# Heater_subassembly_revA.net
KiCad netlist of a schematic drawn in EAGLE
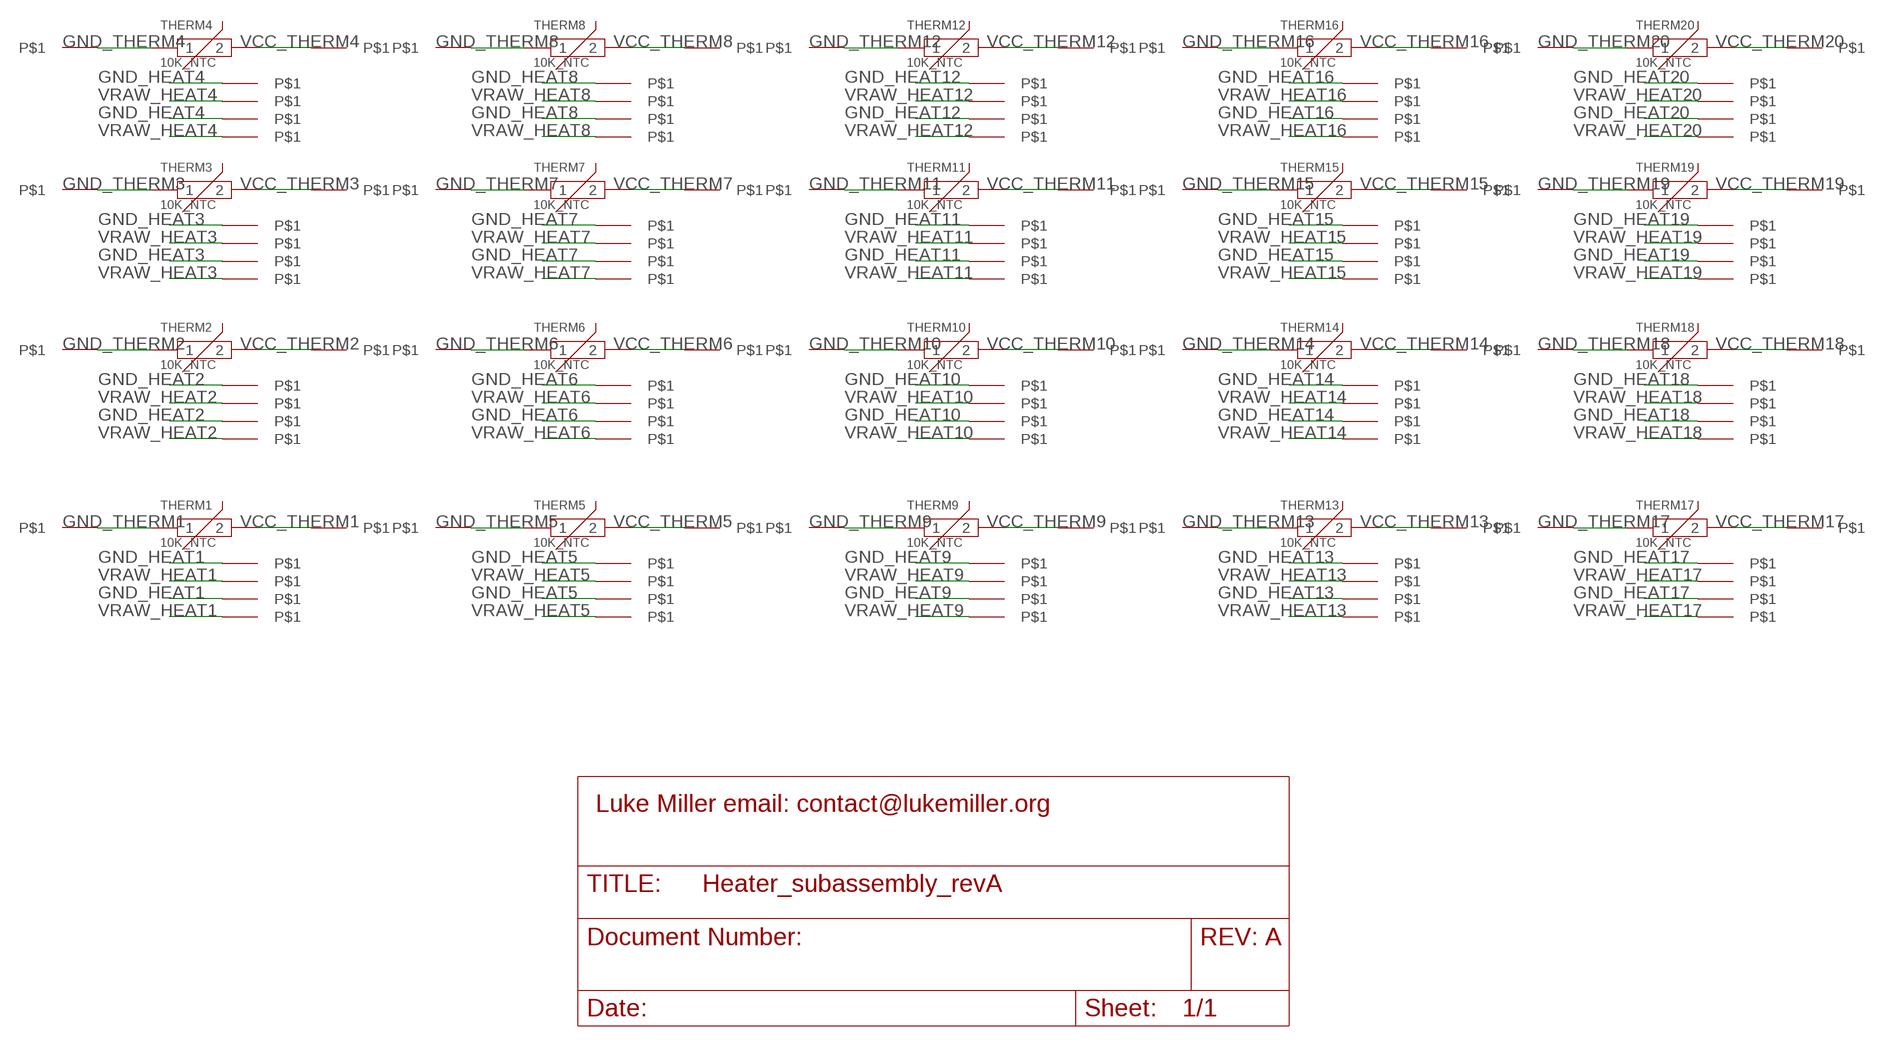
[diagram p0: schematic, sheet 1]

(export (version "E")
  (design (tool "Eeschema 10.0.6"))
  (components
    (comp (ref "GND_HEAT1")
      (value "PINHD-1X1SMALL")
      (footprint "eagle-import:1X01_SMALL")
      (libsource (lib "eagle-import") (part "PINHD-1X1SMALL"))
    )
    (comp (ref "GND_HEAT2")
      (value "PINHD-1X1SMALL")
      (footprint "eagle-import:1X01_SMALL")
      (libsource (lib "eagle-import") (part "PINHD-1X1SMALL"))
    )
    (comp (ref "GND_HEAT3")
      (value "PINHD-1X1SMALL")
      (footprint "eagle-import:1X01_SMALL")
      (libsource (lib "eagle-import") (part "PINHD-1X1SMALL"))
    )
    (comp (ref "GND_HEAT4")
      (value "PINHD-1X1SMALL")
      (footprint "eagle-import:1X01_SMALL")
      (libsource (lib "eagle-import") (part "PINHD-1X1SMALL"))
    )
    (comp (ref "GND_HEAT5")
      (value "PINHD-1X1SMALL")
      (footprint "eagle-import:1X01_SMALL")
      (libsource (lib "eagle-import") (part "PINHD-1X1SMALL"))
    )
    (comp (ref "GND_HEAT6")
      (value "PINHD-1X1SMALL")
      (footprint "eagle-import:1X01_SMALL")
      (libsource (lib "eagle-import") (part "PINHD-1X1SMALL"))
    )
    (comp (ref "GND_HEAT7")
      (value "PINHD-1X1SMALL")
      (footprint "eagle-import:1X01_SMALL")
      (libsource (lib "eagle-import") (part "PINHD-1X1SMALL"))
    )
    (comp (ref "GND_HEAT8")
      (value "PINHD-1X1SMALL")
      (footprint "eagle-import:1X01_SMALL")
      (libsource (lib "eagle-import") (part "PINHD-1X1SMALL"))
    )
    (comp (ref "GND_HEAT9")
      (value "PINHD-1X1SMALL")
      (footprint "eagle-import:1X01_SMALL")
      (libsource (lib "eagle-import") (part "PINHD-1X1SMALL"))
    )
    (comp (ref "GND_HEAT10")
      (value "PINHD-1X1SMALL")
      (footprint "eagle-import:1X01_SMALL")
      (libsource (lib "eagle-import") (part "PINHD-1X1SMALL"))
    )
    (comp (ref "GND_HEAT11")
      (value "PINHD-1X1SMALL")
      (footprint "eagle-import:1X01_SMALL")
      (libsource (lib "eagle-import") (part "PINHD-1X1SMALL"))
    )
    (comp (ref "GND_HEAT12")
      (value "PINHD-1X1SMALL")
      (footprint "eagle-import:1X01_SMALL")
      (libsource (lib "eagle-import") (part "PINHD-1X1SMALL"))
    )
    (comp (ref "GND_HEAT13")
      (value "PINHD-1X1SMALL")
      (footprint "eagle-import:1X01_SMALL")
      (libsource (lib "eagle-import") (part "PINHD-1X1SMALL"))
    )
    (comp (ref "GND_HEAT14")
      (value "PINHD-1X1SMALL")
      (footprint "eagle-import:1X01_SMALL")
      (libsource (lib "eagle-import") (part "PINHD-1X1SMALL"))
    )
    (comp (ref "GND_HEAT15")
      (value "PINHD-1X1SMALL")
      (footprint "eagle-import:1X01_SMALL")
      (libsource (lib "eagle-import") (part "PINHD-1X1SMALL"))
    )
    (comp (ref "GND_HEAT16")
      (value "PINHD-1X1SMALL")
      (footprint "eagle-import:1X01_SMALL")
      (libsource (lib "eagle-import") (part "PINHD-1X1SMALL"))
    )
    (comp (ref "GND_HEAT17")
      (value "PINHD-1X1SMALL")
      (footprint "eagle-import:1X01_SMALL")
      (libsource (lib "eagle-import") (part "PINHD-1X1SMALL"))
    )
    (comp (ref "GND_HEAT18")
      (value "PINHD-1X1SMALL")
      (footprint "eagle-import:1X01_SMALL")
      (libsource (lib "eagle-import") (part "PINHD-1X1SMALL"))
    )
    (comp (ref "GND_HEAT19")
      (value "PINHD-1X1SMALL")
      (footprint "eagle-import:1X01_SMALL")
      (libsource (lib "eagle-import") (part "PINHD-1X1SMALL"))
    )
    (comp (ref "GND_HEAT20")
      (value "PINHD-1X1SMALL")
      (footprint "eagle-import:1X01_SMALL")
      (libsource (lib "eagle-import") (part "PINHD-1X1SMALL"))
    )
    (comp (ref "GND_NICHROME1")
      (value "PINHD-1X10.7MM_DRILL")
      (footprint "eagle-import:1X01_SMALL_0.7")
      (libsource (lib "eagle-import") (part "PINHD-1X10.7MM_DRILL"))
    )
    (comp (ref "GND_NICHROME2")
      (value "PINHD-1X10.7MM_DRILL")
      (footprint "eagle-import:1X01_SMALL_0.7")
      (libsource (lib "eagle-import") (part "PINHD-1X10.7MM_DRILL"))
    )
    (comp (ref "GND_NICHROME3")
      (value "PINHD-1X10.7MM_DRILL")
      (footprint "eagle-import:1X01_SMALL_0.7")
      (libsource (lib "eagle-import") (part "PINHD-1X10.7MM_DRILL"))
    )
    (comp (ref "GND_NICHROME4")
      (value "PINHD-1X10.7MM_DRILL")
      (footprint "eagle-import:1X01_SMALL_0.7")
      (libsource (lib "eagle-import") (part "PINHD-1X10.7MM_DRILL"))
    )
    (comp (ref "GND_NICHROME5")
      (value "PINHD-1X10.7MM_DRILL")
      (footprint "eagle-import:1X01_SMALL_0.7")
      (libsource (lib "eagle-import") (part "PINHD-1X10.7MM_DRILL"))
    )
    (comp (ref "GND_NICHROME6")
      (value "PINHD-1X10.7MM_DRILL")
      (footprint "eagle-import:1X01_SMALL_0.7")
      (libsource (lib "eagle-import") (part "PINHD-1X10.7MM_DRILL"))
    )
    (comp (ref "GND_NICHROME7")
      (value "PINHD-1X10.7MM_DRILL")
      (footprint "eagle-import:1X01_SMALL_0.7")
      (libsource (lib "eagle-import") (part "PINHD-1X10.7MM_DRILL"))
    )
    (comp (ref "GND_NICHROME8")
      (value "PINHD-1X10.7MM_DRILL")
      (footprint "eagle-import:1X01_SMALL_0.7")
      (libsource (lib "eagle-import") (part "PINHD-1X10.7MM_DRILL"))
    )
    (comp (ref "GND_NICHROME9")
      (value "PINHD-1X10.7MM_DRILL")
      (footprint "eagle-import:1X01_SMALL_0.7")
      (libsource (lib "eagle-import") (part "PINHD-1X10.7MM_DRILL"))
    )
    (comp (ref "GND_NICHROME10")
      (value "PINHD-1X10.7MM_DRILL")
      (footprint "eagle-import:1X01_SMALL_0.7")
      (libsource (lib "eagle-import") (part "PINHD-1X10.7MM_DRILL"))
    )
    (comp (ref "GND_NICHROME11")
      (value "PINHD-1X10.7MM_DRILL")
      (footprint "eagle-import:1X01_SMALL_0.7")
      (libsource (lib "eagle-import") (part "PINHD-1X10.7MM_DRILL"))
    )
    (comp (ref "GND_NICHROME12")
      (value "PINHD-1X10.7MM_DRILL")
      (footprint "eagle-import:1X01_SMALL_0.7")
      (libsource (lib "eagle-import") (part "PINHD-1X10.7MM_DRILL"))
    )
    (comp (ref "GND_NICHROME13")
      (value "PINHD-1X10.7MM_DRILL")
      (footprint "eagle-import:1X01_SMALL_0.7")
      (libsource (lib "eagle-import") (part "PINHD-1X10.7MM_DRILL"))
    )
    (comp (ref "GND_NICHROME14")
      (value "PINHD-1X10.7MM_DRILL")
      (footprint "eagle-import:1X01_SMALL_0.7")
      (libsource (lib "eagle-import") (part "PINHD-1X10.7MM_DRILL"))
    )
    (comp (ref "GND_NICHROME15")
      (value "PINHD-1X10.7MM_DRILL")
      (footprint "eagle-import:1X01_SMALL_0.7")
      (libsource (lib "eagle-import") (part "PINHD-1X10.7MM_DRILL"))
    )
    (comp (ref "GND_NICHROME16")
      (value "PINHD-1X10.7MM_DRILL")
      (footprint "eagle-import:1X01_SMALL_0.7")
      (libsource (lib "eagle-import") (part "PINHD-1X10.7MM_DRILL"))
    )
    (comp (ref "GND_NICHROME17")
      (value "PINHD-1X10.7MM_DRILL")
      (footprint "eagle-import:1X01_SMALL_0.7")
      (libsource (lib "eagle-import") (part "PINHD-1X10.7MM_DRILL"))
    )
    (comp (ref "GND_NICHROME18")
      (value "PINHD-1X10.7MM_DRILL")
      (footprint "eagle-import:1X01_SMALL_0.7")
      (libsource (lib "eagle-import") (part "PINHD-1X10.7MM_DRILL"))
    )
    (comp (ref "GND_NICHROME19")
      (value "PINHD-1X10.7MM_DRILL")
      (footprint "eagle-import:1X01_SMALL_0.7")
      (libsource (lib "eagle-import") (part "PINHD-1X10.7MM_DRILL"))
    )
    (comp (ref "GND_NICHROME20")
      (value "PINHD-1X10.7MM_DRILL")
      (footprint "eagle-import:1X01_SMALL_0.7")
      (libsource (lib "eagle-import") (part "PINHD-1X10.7MM_DRILL"))
    )
    (comp (ref "GND_THERM1")
      (value "PINHD-1X1SMALL")
      (footprint "eagle-import:1X01_SMALL")
      (libsource (lib "eagle-import") (part "PINHD-1X1SMALL"))
    )
    (comp (ref "GND_THERM2")
      (value "PINHD-1X1SMALL")
      (footprint "eagle-import:1X01_SMALL")
      (libsource (lib "eagle-import") (part "PINHD-1X1SMALL"))
    )
    (comp (ref "GND_THERM3")
      (value "PINHD-1X1SMALL")
      (footprint "eagle-import:1X01_SMALL")
      (libsource (lib "eagle-import") (part "PINHD-1X1SMALL"))
    )
    (comp (ref "GND_THERM4")
      (value "PINHD-1X1SMALL")
      (footprint "eagle-import:1X01_SMALL")
      (libsource (lib "eagle-import") (part "PINHD-1X1SMALL"))
    )
    (comp (ref "GND_THERM5")
      (value "PINHD-1X1SMALL")
      (footprint "eagle-import:1X01_SMALL")
      (libsource (lib "eagle-import") (part "PINHD-1X1SMALL"))
    )
    (comp (ref "GND_THERM6")
      (value "PINHD-1X1SMALL")
      (footprint "eagle-import:1X01_SMALL")
      (libsource (lib "eagle-import") (part "PINHD-1X1SMALL"))
    )
    (comp (ref "GND_THERM7")
      (value "PINHD-1X1SMALL")
      (footprint "eagle-import:1X01_SMALL")
      (libsource (lib "eagle-import") (part "PINHD-1X1SMALL"))
    )
    (comp (ref "GND_THERM8")
      (value "PINHD-1X1SMALL")
      (footprint "eagle-import:1X01_SMALL")
      (libsource (lib "eagle-import") (part "PINHD-1X1SMALL"))
    )
    (comp (ref "GND_THERM9")
      (value "PINHD-1X1SMALL")
      (footprint "eagle-import:1X01_SMALL")
      (libsource (lib "eagle-import") (part "PINHD-1X1SMALL"))
    )
    (comp (ref "GND_THERM10")
      (value "PINHD-1X1SMALL")
      (footprint "eagle-import:1X01_SMALL")
      (libsource (lib "eagle-import") (part "PINHD-1X1SMALL"))
    )
    (comp (ref "GND_THERM11")
      (value "PINHD-1X1SMALL")
      (footprint "eagle-import:1X01_SMALL")
      (libsource (lib "eagle-import") (part "PINHD-1X1SMALL"))
    )
    (comp (ref "GND_THERM12")
      (value "PINHD-1X1SMALL")
      (footprint "eagle-import:1X01_SMALL")
      (libsource (lib "eagle-import") (part "PINHD-1X1SMALL"))
    )
    (comp (ref "GND_THERM13")
      (value "PINHD-1X1SMALL")
      (footprint "eagle-import:1X01_SMALL")
      (libsource (lib "eagle-import") (part "PINHD-1X1SMALL"))
    )
    (comp (ref "GND_THERM14")
      (value "PINHD-1X1SMALL")
      (footprint "eagle-import:1X01_SMALL")
      (libsource (lib "eagle-import") (part "PINHD-1X1SMALL"))
    )
    (comp (ref "GND_THERM16")
      (value "PINHD-1X1SMALL")
      (footprint "eagle-import:1X01_SMALL")
      (libsource (lib "eagle-import") (part "PINHD-1X1SMALL"))
    )
    (comp (ref "GND_THERM17")
      (value "PINHD-1X1SMALL")
      (footprint "eagle-import:1X01_SMALL")
      (libsource (lib "eagle-import") (part "PINHD-1X1SMALL"))
    )
    (comp (ref "GND_THERM18")
      (value "PINHD-1X1SMALL")
      (footprint "eagle-import:1X01_SMALL")
      (libsource (lib "eagle-import") (part "PINHD-1X1SMALL"))
    )
    (comp (ref "GND_THERM19")
      (value "PINHD-1X1SMALL")
      (footprint "eagle-import:1X01_SMALL")
      (libsource (lib "eagle-import") (part "PINHD-1X1SMALL"))
    )
    (comp (ref "GND_THERM20")
      (value "PINHD-1X1SMALL")
      (footprint "eagle-import:1X01_SMALL")
      (libsource (lib "eagle-import") (part "PINHD-1X1SMALL"))
    )
    (comp (ref "THERM1")
      (value "10K_NTC")
      (footprint "eagle-import:R0603_THERMISTOR")
      (libsource (lib "eagle-import") (part "THERMISTOR_NTC_SMD0603"))
    )
    (comp (ref "THERM2")
      (value "10K_NTC")
      (footprint "eagle-import:R0603_THERMISTOR")
      (libsource (lib "eagle-import") (part "THERMISTOR_NTC_SMD0603"))
    )
    (comp (ref "THERM3")
      (value "10K_NTC")
      (footprint "eagle-import:R0603_THERMISTOR")
      (libsource (lib "eagle-import") (part "THERMISTOR_NTC_SMD0603"))
    )
    (comp (ref "THERM4")
      (value "10K_NTC")
      (footprint "eagle-import:R0603_THERMISTOR")
      (libsource (lib "eagle-import") (part "THERMISTOR_NTC_SMD0603"))
    )
    (comp (ref "THERM5")
      (value "10K_NTC")
      (footprint "eagle-import:R0603_THERMISTOR")
      (libsource (lib "eagle-import") (part "THERMISTOR_NTC_SMD0603"))
    )
    (comp (ref "THERM6")
      (value "10K_NTC")
      (footprint "eagle-import:R0603_THERMISTOR")
      (libsource (lib "eagle-import") (part "THERMISTOR_NTC_SMD0603"))
    )
    (comp (ref "THERM7")
      (value "10K_NTC")
      (footprint "eagle-import:R0603_THERMISTOR")
      (libsource (lib "eagle-import") (part "THERMISTOR_NTC_SMD0603"))
    )
    (comp (ref "THERM8")
      (value "10K_NTC")
      (footprint "eagle-import:R0603_THERMISTOR")
      (libsource (lib "eagle-import") (part "THERMISTOR_NTC_SMD0603"))
    )
    (comp (ref "THERM9")
      (value "10K_NTC")
      (footprint "eagle-import:R0603_THERMISTOR")
      (libsource (lib "eagle-import") (part "THERMISTOR_NTC_SMD0603"))
    )
    (comp (ref "THERM10")
      (value "10K_NTC")
      (footprint "eagle-import:R0603_THERMISTOR")
      (libsource (lib "eagle-import") (part "THERMISTOR_NTC_SMD0603"))
    )
    (comp (ref "THERM11")
      (value "10K_NTC")
      (footprint "eagle-import:R0603_THERMISTOR")
      (libsource (lib "eagle-import") (part "THERMISTOR_NTC_SMD0603"))
    )
    (comp (ref "THERM12")
      (value "10K_NTC")
      (footprint "eagle-import:R0603_THERMISTOR")
      (libsource (lib "eagle-import") (part "THERMISTOR_NTC_SMD0603"))
    )
    (comp (ref "THERM13")
      (value "10K_NTC")
      (footprint "eagle-import:R0603_THERMISTOR")
      (libsource (lib "eagle-import") (part "THERMISTOR_NTC_SMD0603"))
    )
    (comp (ref "THERM14")
      (value "10K_NTC")
      (footprint "eagle-import:R0603_THERMISTOR")
      (libsource (lib "eagle-import") (part "THERMISTOR_NTC_SMD0603"))
    )
    (comp (ref "THERM15")
      (value "10K_NTC")
      (footprint "eagle-import:R0603_THERMISTOR")
      (libsource (lib "eagle-import") (part "THERMISTOR_NTC_SMD0603"))
    )
    (comp (ref "THERM16")
      (value "10K_NTC")
      (footprint "eagle-import:R0603_THERMISTOR")
      (libsource (lib "eagle-import") (part "THERMISTOR_NTC_SMD0603"))
    )
    (comp (ref "THERM17")
      (value "10K_NTC")
      (footprint "eagle-import:R0603_THERMISTOR")
      (libsource (lib "eagle-import") (part "THERMISTOR_NTC_SMD0603"))
    )
    (comp (ref "THERM18")
      (value "10K_NTC")
      (footprint "eagle-import:R0603_THERMISTOR")
      (libsource (lib "eagle-import") (part "THERMISTOR_NTC_SMD0603"))
    )
    (comp (ref "THERM19")
      (value "10K_NTC")
      (footprint "eagle-import:R0603_THERMISTOR")
      (libsource (lib "eagle-import") (part "THERMISTOR_NTC_SMD0603"))
    )
    (comp (ref "THERM20")
      (value "10K_NTC")
      (footprint "eagle-import:R0603_THERMISTOR")
      (libsource (lib "eagle-import") (part "THERMISTOR_NTC_SMD0603"))
    )
    (comp (ref "U$30")
      (value "PINHD-1X1SMALL")
      (footprint "eagle-import:1X01_SMALL")
      (libsource (lib "eagle-import") (part "PINHD-1X1SMALL"))
    )
    (comp (ref "VCC_THERM1")
      (value "PINHD-1X1SMALL")
      (footprint "eagle-import:1X01_SMALL")
      (libsource (lib "eagle-import") (part "PINHD-1X1SMALL"))
    )
    (comp (ref "VCC_THERM2")
      (value "PINHD-1X1SMALL")
      (footprint "eagle-import:1X01_SMALL")
      (libsource (lib "eagle-import") (part "PINHD-1X1SMALL"))
    )
    (comp (ref "VCC_THERM3")
      (value "PINHD-1X1SMALL")
      (footprint "eagle-import:1X01_SMALL")
      (libsource (lib "eagle-import") (part "PINHD-1X1SMALL"))
    )
    (comp (ref "VCC_THERM4")
      (value "PINHD-1X1SMALL")
      (footprint "eagle-import:1X01_SMALL")
      (libsource (lib "eagle-import") (part "PINHD-1X1SMALL"))
    )
    (comp (ref "VCC_THERM5")
      (value "PINHD-1X1SMALL")
      (footprint "eagle-import:1X01_SMALL")
      (libsource (lib "eagle-import") (part "PINHD-1X1SMALL"))
    )
    (comp (ref "VCC_THERM6")
      (value "PINHD-1X1SMALL")
      (footprint "eagle-import:1X01_SMALL")
      (libsource (lib "eagle-import") (part "PINHD-1X1SMALL"))
    )
    (comp (ref "VCC_THERM7")
      (value "PINHD-1X1SMALL")
      (footprint "eagle-import:1X01_SMALL")
      (libsource (lib "eagle-import") (part "PINHD-1X1SMALL"))
    )
    (comp (ref "VCC_THERM8")
      (value "PINHD-1X1SMALL")
      (footprint "eagle-import:1X01_SMALL")
      (libsource (lib "eagle-import") (part "PINHD-1X1SMALL"))
    )
    (comp (ref "VCC_THERM9")
      (value "PINHD-1X1SMALL")
      (footprint "eagle-import:1X01_SMALL")
      (libsource (lib "eagle-import") (part "PINHD-1X1SMALL"))
    )
    (comp (ref "VCC_THERM10")
      (value "PINHD-1X1SMALL")
      (footprint "eagle-import:1X01_SMALL")
      (libsource (lib "eagle-import") (part "PINHD-1X1SMALL"))
    )
    (comp (ref "VCC_THERM11")
      (value "PINHD-1X1SMALL")
      (footprint "eagle-import:1X01_SMALL")
      (libsource (lib "eagle-import") (part "PINHD-1X1SMALL"))
    )
    (comp (ref "VCC_THERM12")
      (value "PINHD-1X1SMALL")
      (footprint "eagle-import:1X01_SMALL")
      (libsource (lib "eagle-import") (part "PINHD-1X1SMALL"))
    )
    (comp (ref "VCC_THERM13")
      (value "PINHD-1X1SMALL")
      (footprint "eagle-import:1X01_SMALL")
      (libsource (lib "eagle-import") (part "PINHD-1X1SMALL"))
    )
    (comp (ref "VCC_THERM14")
      (value "PINHD-1X1SMALL")
      (footprint "eagle-import:1X01_SMALL")
      (libsource (lib "eagle-import") (part "PINHD-1X1SMALL"))
    )
    (comp (ref "VCC_THERM15")
      (value "PINHD-1X1SMALL")
      (footprint "eagle-import:1X01_SMALL")
      (libsource (lib "eagle-import") (part "PINHD-1X1SMALL"))
    )
    (comp (ref "VCC_THERM16")
      (value "PINHD-1X1SMALL")
      (footprint "eagle-import:1X01_SMALL")
      (libsource (lib "eagle-import") (part "PINHD-1X1SMALL"))
    )
    (comp (ref "VCC_THERM17")
      (value "PINHD-1X1SMALL")
      (footprint "eagle-import:1X01_SMALL")
      (libsource (lib "eagle-import") (part "PINHD-1X1SMALL"))
    )
    (comp (ref "VCC_THERM18")
      (value "PINHD-1X1SMALL")
      (footprint "eagle-import:1X01_SMALL")
      (libsource (lib "eagle-import") (part "PINHD-1X1SMALL"))
    )
    (comp (ref "VCC_THERM19")
      (value "PINHD-1X1SMALL")
      (footprint "eagle-import:1X01_SMALL")
      (libsource (lib "eagle-import") (part "PINHD-1X1SMALL"))
    )
    (comp (ref "VCC_THERM20")
      (value "PINHD-1X1SMALL")
      (footprint "eagle-import:1X01_SMALL")
      (libsource (lib "eagle-import") (part "PINHD-1X1SMALL"))
    )
    (comp (ref "VRAW_HEAT1")
      (value "PINHD-1X1SMALL")
      (footprint "eagle-import:1X01_SMALL")
      (libsource (lib "eagle-import") (part "PINHD-1X1SMALL"))
    )
    (comp (ref "VRAW_HEAT2")
      (value "PINHD-1X1SMALL")
      (footprint "eagle-import:1X01_SMALL")
      (libsource (lib "eagle-import") (part "PINHD-1X1SMALL"))
    )
    (comp (ref "VRAW_HEAT3")
      (value "PINHD-1X1SMALL")
      (footprint "eagle-import:1X01_SMALL")
      (libsource (lib "eagle-import") (part "PINHD-1X1SMALL"))
    )
    (comp (ref "VRAW_HEAT4")
      (value "PINHD-1X1SMALL")
      (footprint "eagle-import:1X01_SMALL")
      (libsource (lib "eagle-import") (part "PINHD-1X1SMALL"))
    )
    (comp (ref "VRAW_HEAT5")
      (value "PINHD-1X1SMALL")
      (footprint "eagle-import:1X01_SMALL")
      (libsource (lib "eagle-import") (part "PINHD-1X1SMALL"))
    )
    (comp (ref "VRAW_HEAT6")
      (value "PINHD-1X1SMALL")
      (footprint "eagle-import:1X01_SMALL")
      (libsource (lib "eagle-import") (part "PINHD-1X1SMALL"))
    )
    (comp (ref "VRAW_HEAT7")
      (value "PINHD-1X1SMALL")
      (footprint "eagle-import:1X01_SMALL")
      (libsource (lib "eagle-import") (part "PINHD-1X1SMALL"))
    )
    (comp (ref "VRAW_HEAT8")
      (value "PINHD-1X1SMALL")
      (footprint "eagle-import:1X01_SMALL")
      (libsource (lib "eagle-import") (part "PINHD-1X1SMALL"))
    )
    (comp (ref "VRAW_HEAT9")
      (value "PINHD-1X1SMALL")
      (footprint "eagle-import:1X01_SMALL")
      (libsource (lib "eagle-import") (part "PINHD-1X1SMALL"))
    )
    (comp (ref "VRAW_HEAT10")
      (value "PINHD-1X1SMALL")
      (footprint "eagle-import:1X01_SMALL")
      (libsource (lib "eagle-import") (part "PINHD-1X1SMALL"))
    )
    (comp (ref "VRAW_HEAT11")
      (value "PINHD-1X1SMALL")
      (footprint "eagle-import:1X01_SMALL")
      (libsource (lib "eagle-import") (part "PINHD-1X1SMALL"))
    )
    (comp (ref "VRAW_HEAT12")
      (value "PINHD-1X1SMALL")
      (footprint "eagle-import:1X01_SMALL")
      (libsource (lib "eagle-import") (part "PINHD-1X1SMALL"))
    )
    (comp (ref "VRAW_HEAT13")
      (value "PINHD-1X1SMALL")
      (footprint "eagle-import:1X01_SMALL")
      (libsource (lib "eagle-import") (part "PINHD-1X1SMALL"))
    )
    (comp (ref "VRAW_HEAT14")
      (value "PINHD-1X1SMALL")
      (footprint "eagle-import:1X01_SMALL")
      (libsource (lib "eagle-import") (part "PINHD-1X1SMALL"))
    )
    (comp (ref "VRAW_HEAT15")
      (value "PINHD-1X1SMALL")
      (footprint "eagle-import:1X01_SMALL")
      (libsource (lib "eagle-import") (part "PINHD-1X1SMALL"))
    )
    (comp (ref "VRAW_HEAT16")
      (value "PINHD-1X1SMALL")
      (footprint "eagle-import:1X01_SMALL")
      (libsource (lib "eagle-import") (part "PINHD-1X1SMALL"))
    )
    (comp (ref "VRAW_HEAT17")
      (value "PINHD-1X1SMALL")
      (footprint "eagle-import:1X01_SMALL")
      (libsource (lib "eagle-import") (part "PINHD-1X1SMALL"))
    )
    (comp (ref "VRAW_HEAT18")
      (value "PINHD-1X1SMALL")
      (footprint "eagle-import:1X01_SMALL")
      (libsource (lib "eagle-import") (part "PINHD-1X1SMALL"))
    )
    (comp (ref "VRAW_HEAT19")
      (value "PINHD-1X1SMALL")
      (footprint "eagle-import:1X01_SMALL")
      (libsource (lib "eagle-import") (part "PINHD-1X1SMALL"))
    )
    (comp (ref "VRAW_HEAT20")
      (value "PINHD-1X1SMALL")
      (footprint "eagle-import:1X01_SMALL")
      (libsource (lib "eagle-import") (part "PINHD-1X1SMALL"))
    )
    (comp (ref "VRAW_NICHROME1")
      (value "PINHD-1X10.7MM_DRILL")
      (footprint "eagle-import:1X01_SMALL_0.7")
      (libsource (lib "eagle-import") (part "PINHD-1X10.7MM_DRILL"))
    )
    (comp (ref "VRAW_NICHROME2")
      (value "PINHD-1X10.7MM_DRILL")
      (footprint "eagle-import:1X01_SMALL_0.7")
      (libsource (lib "eagle-import") (part "PINHD-1X10.7MM_DRILL"))
    )
    (comp (ref "VRAW_NICHROME3")
      (value "PINHD-1X10.7MM_DRILL")
      (footprint "eagle-import:1X01_SMALL_0.7")
      (libsource (lib "eagle-import") (part "PINHD-1X10.7MM_DRILL"))
    )
    (comp (ref "VRAW_NICHROME4")
      (value "PINHD-1X10.7MM_DRILL")
      (footprint "eagle-import:1X01_SMALL_0.7")
      (libsource (lib "eagle-import") (part "PINHD-1X10.7MM_DRILL"))
    )
    (comp (ref "VRAW_NICHROME5")
      (value "PINHD-1X10.7MM_DRILL")
      (footprint "eagle-import:1X01_SMALL_0.7")
      (libsource (lib "eagle-import") (part "PINHD-1X10.7MM_DRILL"))
    )
    (comp (ref "VRAW_NICHROME6")
      (value "PINHD-1X10.7MM_DRILL")
      (footprint "eagle-import:1X01_SMALL_0.7")
      (libsource (lib "eagle-import") (part "PINHD-1X10.7MM_DRILL"))
    )
    (comp (ref "VRAW_NICHROME7")
      (value "PINHD-1X10.7MM_DRILL")
      (footprint "eagle-import:1X01_SMALL_0.7")
      (libsource (lib "eagle-import") (part "PINHD-1X10.7MM_DRILL"))
    )
    (comp (ref "VRAW_NICHROME8")
      (value "PINHD-1X10.7MM_DRILL")
      (footprint "eagle-import:1X01_SMALL_0.7")
      (libsource (lib "eagle-import") (part "PINHD-1X10.7MM_DRILL"))
    )
    (comp (ref "VRAW_NICHROME9")
      (value "PINHD-1X10.7MM_DRILL")
      (footprint "eagle-import:1X01_SMALL_0.7")
      (libsource (lib "eagle-import") (part "PINHD-1X10.7MM_DRILL"))
    )
    (comp (ref "VRAW_NICHROME10")
      (value "PINHD-1X10.7MM_DRILL")
      (footprint "eagle-import:1X01_SMALL_0.7")
      (libsource (lib "eagle-import") (part "PINHD-1X10.7MM_DRILL"))
    )
    (comp (ref "VRAW_NICHROME11")
      (value "PINHD-1X10.7MM_DRILL")
      (footprint "eagle-import:1X01_SMALL_0.7")
      (libsource (lib "eagle-import") (part "PINHD-1X10.7MM_DRILL"))
    )
    (comp (ref "VRAW_NICHROME12")
      (value "PINHD-1X10.7MM_DRILL")
      (footprint "eagle-import:1X01_SMALL_0.7")
      (libsource (lib "eagle-import") (part "PINHD-1X10.7MM_DRILL"))
    )
    (comp (ref "VRAW_NICHROME13")
      (value "PINHD-1X10.7MM_DRILL")
      (footprint "eagle-import:1X01_SMALL_0.7")
      (libsource (lib "eagle-import") (part "PINHD-1X10.7MM_DRILL"))
    )
    (comp (ref "VRAW_NICHROME14")
      (value "PINHD-1X10.7MM_DRILL")
      (footprint "eagle-import:1X01_SMALL_0.7")
      (libsource (lib "eagle-import") (part "PINHD-1X10.7MM_DRILL"))
    )
    (comp (ref "VRAW_NICHROME15")
      (value "PINHD-1X10.7MM_DRILL")
      (footprint "eagle-import:1X01_SMALL_0.7")
      (libsource (lib "eagle-import") (part "PINHD-1X10.7MM_DRILL"))
    )
    (comp (ref "VRAW_NICHROME16")
      (value "PINHD-1X10.7MM_DRILL")
      (footprint "eagle-import:1X01_SMALL_0.7")
      (libsource (lib "eagle-import") (part "PINHD-1X10.7MM_DRILL"))
    )
    (comp (ref "VRAW_NICHROME17")
      (value "PINHD-1X10.7MM_DRILL")
      (footprint "eagle-import:1X01_SMALL_0.7")
      (libsource (lib "eagle-import") (part "PINHD-1X10.7MM_DRILL"))
    )
    (comp (ref "VRAW_NICHROME18")
      (value "PINHD-1X10.7MM_DRILL")
      (footprint "eagle-import:1X01_SMALL_0.7")
      (libsource (lib "eagle-import") (part "PINHD-1X10.7MM_DRILL"))
    )
    (comp (ref "VRAW_NICHROME19")
      (value "PINHD-1X10.7MM_DRILL")
      (footprint "eagle-import:1X01_SMALL_0.7")
      (libsource (lib "eagle-import") (part "PINHD-1X10.7MM_DRILL"))
    )
    (comp (ref "VRAW_NICHROME20")
      (value "PINHD-1X10.7MM_DRILL")
      (footprint "eagle-import:1X01_SMALL_0.7")
      (libsource (lib "eagle-import") (part "PINHD-1X10.7MM_DRILL"))
    )
  )
  (nets
    (net (code "1") (name "/GND_HEAT1") (class "Default")
      (node (ref "GND_HEAT1") (pin "1") (pinfunction "P$1_1") (pintype "bidirectional"))
      (node (ref "GND_NICHROME1") (pin "P$1") (pinfunction "P$1_P$1") (pintype "bidirectional"))
    )
    (net (code "2") (name "/GND_HEAT2") (class "Default")
      (node (ref "GND_HEAT2") (pin "1") (pinfunction "P$1_1") (pintype "bidirectional"))
      (node (ref "GND_NICHROME2") (pin "P$1") (pinfunction "P$1_P$1") (pintype "bidirectional"))
    )
    (net (code "3") (name "/GND_HEAT3") (class "Default")
      (node (ref "GND_HEAT3") (pin "1") (pinfunction "P$1_1") (pintype "bidirectional"))
      (node (ref "GND_NICHROME3") (pin "P$1") (pinfunction "P$1_P$1") (pintype "bidirectional"))
    )
    (net (code "4") (name "/GND_HEAT4") (class "Default")
      (node (ref "GND_HEAT4") (pin "1") (pinfunction "P$1_1") (pintype "bidirectional"))
      (node (ref "GND_NICHROME4") (pin "P$1") (pinfunction "P$1_P$1") (pintype "bidirectional"))
    )
    (net (code "5") (name "/GND_HEAT5") (class "Default")
      (node (ref "GND_HEAT5") (pin "1") (pinfunction "P$1_1") (pintype "bidirectional"))
      (node (ref "GND_NICHROME5") (pin "P$1") (pinfunction "P$1_P$1") (pintype "bidirectional"))
    )
    (net (code "6") (name "/GND_HEAT6") (class "Default")
      (node (ref "GND_HEAT6") (pin "1") (pinfunction "P$1_1") (pintype "bidirectional"))
      (node (ref "GND_NICHROME6") (pin "P$1") (pinfunction "P$1_P$1") (pintype "bidirectional"))
    )
    (net (code "7") (name "/GND_HEAT7") (class "Default")
      (node (ref "GND_HEAT7") (pin "1") (pinfunction "P$1_1") (pintype "bidirectional"))
      (node (ref "GND_NICHROME7") (pin "P$1") (pinfunction "P$1_P$1") (pintype "bidirectional"))
    )
    (net (code "8") (name "/GND_HEAT8") (class "Default")
      (node (ref "GND_HEAT8") (pin "1") (pinfunction "P$1_1") (pintype "bidirectional"))
      (node (ref "GND_NICHROME8") (pin "P$1") (pinfunction "P$1_P$1") (pintype "bidirectional"))
    )
    (net (code "9") (name "/GND_HEAT9") (class "Default")
      (node (ref "GND_HEAT9") (pin "1") (pinfunction "P$1_1") (pintype "bidirectional"))
      (node (ref "GND_NICHROME9") (pin "P$1") (pinfunction "P$1_P$1") (pintype "bidirectional"))
    )
    (net (code "10") (name "/GND_HEAT10") (class "Default")
      (node (ref "GND_HEAT10") (pin "1") (pinfunction "P$1_1") (pintype "bidirectional"))
      (node (ref "GND_NICHROME10") (pin "P$1") (pinfunction "P$1_P$1") (pintype "bidirectional"))
    )
    (net (code "11") (name "/GND_HEAT11") (class "Default")
      (node (ref "GND_HEAT11") (pin "1") (pinfunction "P$1_1") (pintype "bidirectional"))
      (node (ref "GND_NICHROME11") (pin "P$1") (pinfunction "P$1_P$1") (pintype "bidirectional"))
    )
    (net (code "12") (name "/GND_HEAT12") (class "Default")
      (node (ref "GND_HEAT12") (pin "1") (pinfunction "P$1_1") (pintype "bidirectional"))
      (node (ref "GND_NICHROME12") (pin "P$1") (pinfunction "P$1_P$1") (pintype "bidirectional"))
    )
    (net (code "13") (name "/GND_HEAT13") (class "Default")
      (node (ref "GND_HEAT13") (pin "1") (pinfunction "P$1_1") (pintype "bidirectional"))
      (node (ref "GND_NICHROME13") (pin "P$1") (pinfunction "P$1_P$1") (pintype "bidirectional"))
    )
    (net (code "14") (name "/GND_HEAT14") (class "Default")
      (node (ref "GND_HEAT14") (pin "1") (pinfunction "P$1_1") (pintype "bidirectional"))
      (node (ref "GND_NICHROME14") (pin "P$1") (pinfunction "P$1_P$1") (pintype "bidirectional"))
    )
    (net (code "15") (name "/GND_HEAT15") (class "Default")
      (node (ref "GND_HEAT15") (pin "1") (pinfunction "P$1_1") (pintype "bidirectional"))
      (node (ref "GND_NICHROME15") (pin "P$1") (pinfunction "P$1_P$1") (pintype "bidirectional"))
    )
    (net (code "16") (name "/GND_HEAT16") (class "Default")
      (node (ref "GND_HEAT16") (pin "1") (pinfunction "P$1_1") (pintype "bidirectional"))
      (node (ref "GND_NICHROME16") (pin "P$1") (pinfunction "P$1_P$1") (pintype "bidirectional"))
    )
    (net (code "17") (name "/GND_HEAT17") (class "Default")
      (node (ref "GND_HEAT17") (pin "1") (pinfunction "P$1_1") (pintype "bidirectional"))
      (node (ref "GND_NICHROME17") (pin "P$1") (pinfunction "P$1_P$1") (pintype "bidirectional"))
    )
    (net (code "18") (name "/GND_HEAT18") (class "Default")
      (node (ref "GND_HEAT18") (pin "1") (pinfunction "P$1_1") (pintype "bidirectional"))
      (node (ref "GND_NICHROME18") (pin "P$1") (pinfunction "P$1_P$1") (pintype "bidirectional"))
    )
    (net (code "19") (name "/GND_HEAT19") (class "Default")
      (node (ref "GND_HEAT19") (pin "1") (pinfunction "P$1_1") (pintype "bidirectional"))
      (node (ref "GND_NICHROME19") (pin "P$1") (pinfunction "P$1_P$1") (pintype "bidirectional"))
    )
    (net (code "20") (name "/GND_HEAT20") (class "Default")
      (node (ref "GND_HEAT20") (pin "1") (pinfunction "P$1_1") (pintype "bidirectional"))
      (node (ref "GND_NICHROME20") (pin "P$1") (pinfunction "P$1_P$1") (pintype "bidirectional"))
    )
    (net (code "21") (name "/GND_THERM1") (class "Default")
      (node (ref "GND_THERM1") (pin "1") (pinfunction "P$1_1") (pintype "bidirectional"))
      (node (ref "THERM1") (pin "1") (pinfunction "1_1") (pintype "bidirectional"))
    )
    (net (code "22") (name "/GND_THERM2") (class "Default")
      (node (ref "GND_THERM2") (pin "1") (pinfunction "P$1_1") (pintype "bidirectional"))
      (node (ref "THERM2") (pin "1") (pinfunction "1_1") (pintype "bidirectional"))
    )
    (net (code "23") (name "/GND_THERM3") (class "Default")
      (node (ref "GND_THERM3") (pin "1") (pinfunction "P$1_1") (pintype "bidirectional"))
      (node (ref "THERM3") (pin "1") (pinfunction "1_1") (pintype "bidirectional"))
    )
    (net (code "24") (name "/GND_THERM4") (class "Default")
      (node (ref "GND_THERM4") (pin "1") (pinfunction "P$1_1") (pintype "bidirectional"))
      (node (ref "THERM4") (pin "1") (pinfunction "1_1") (pintype "bidirectional"))
    )
    (net (code "25") (name "/GND_THERM5") (class "Default")
      (node (ref "GND_THERM5") (pin "1") (pinfunction "P$1_1") (pintype "bidirectional"))
      (node (ref "THERM5") (pin "1") (pinfunction "1_1") (pintype "bidirectional"))
    )
    (net (code "26") (name "/GND_THERM6") (class "Default")
      (node (ref "GND_THERM6") (pin "1") (pinfunction "P$1_1") (pintype "bidirectional"))
      (node (ref "THERM6") (pin "1") (pinfunction "1_1") (pintype "bidirectional"))
    )
    (net (code "27") (name "/GND_THERM7") (class "Default")
      (node (ref "GND_THERM7") (pin "1") (pinfunction "P$1_1") (pintype "bidirectional"))
      (node (ref "THERM7") (pin "1") (pinfunction "1_1") (pintype "bidirectional"))
    )
    (net (code "28") (name "/GND_THERM8") (class "Default")
      (node (ref "GND_THERM8") (pin "1") (pinfunction "P$1_1") (pintype "bidirectional"))
      (node (ref "THERM8") (pin "1") (pinfunction "1_1") (pintype "bidirectional"))
    )
    (net (code "29") (name "/GND_THERM9") (class "Default")
      (node (ref "GND_THERM9") (pin "1") (pinfunction "P$1_1") (pintype "bidirectional"))
      (node (ref "THERM9") (pin "1") (pinfunction "1_1") (pintype "bidirectional"))
    )
    (net (code "30") (name "/GND_THERM10") (class "Default")
      (node (ref "GND_THERM10") (pin "1") (pinfunction "P$1_1") (pintype "bidirectional"))
      (node (ref "THERM10") (pin "1") (pinfunction "1_1") (pintype "bidirectional"))
    )
    (net (code "31") (name "/GND_THERM11") (class "Default")
      (node (ref "GND_THERM11") (pin "1") (pinfunction "P$1_1") (pintype "bidirectional"))
      (node (ref "THERM11") (pin "1") (pinfunction "1_1") (pintype "bidirectional"))
    )
    (net (code "32") (name "/GND_THERM12") (class "Default")
      (node (ref "GND_THERM12") (pin "1") (pinfunction "P$1_1") (pintype "bidirectional"))
      (node (ref "THERM12") (pin "1") (pinfunction "1_1") (pintype "bidirectional"))
    )
    (net (code "33") (name "/GND_THERM13") (class "Default")
      (node (ref "GND_THERM13") (pin "1") (pinfunction "P$1_1") (pintype "bidirectional"))
      (node (ref "THERM13") (pin "1") (pinfunction "1_1") (pintype "bidirectional"))
    )
    (net (code "34") (name "/GND_THERM14") (class "Default")
      (node (ref "GND_THERM14") (pin "1") (pinfunction "P$1_1") (pintype "bidirectional"))
      (node (ref "THERM14") (pin "1") (pinfunction "1_1") (pintype "bidirectional"))
    )
    (net (code "35") (name "/GND_THERM15") (class "Default")
      (node (ref "THERM15") (pin "1") (pinfunction "1_1") (pintype "bidirectional"))
      (node (ref "U$30") (pin "1") (pinfunction "P$1_1") (pintype "bidirectional"))
    )
    (net (code "36") (name "/GND_THERM16") (class "Default")
      (node (ref "GND_THERM16") (pin "1") (pinfunction "P$1_1") (pintype "bidirectional"))
      (node (ref "THERM16") (pin "1") (pinfunction "1_1") (pintype "bidirectional"))
    )
    (net (code "37") (name "/GND_THERM17") (class "Default")
      (node (ref "GND_THERM17") (pin "1") (pinfunction "P$1_1") (pintype "bidirectional"))
      (node (ref "THERM17") (pin "1") (pinfunction "1_1") (pintype "bidirectional"))
    )
    (net (code "38") (name "/GND_THERM18") (class "Default")
      (node (ref "GND_THERM18") (pin "1") (pinfunction "P$1_1") (pintype "bidirectional"))
      (node (ref "THERM18") (pin "1") (pinfunction "1_1") (pintype "bidirectional"))
    )
    (net (code "39") (name "/GND_THERM19") (class "Default")
      (node (ref "GND_THERM19") (pin "1") (pinfunction "P$1_1") (pintype "bidirectional"))
      (node (ref "THERM19") (pin "1") (pinfunction "1_1") (pintype "bidirectional"))
    )
    (net (code "40") (name "/GND_THERM20") (class "Default")
      (node (ref "GND_THERM20") (pin "1") (pinfunction "P$1_1") (pintype "bidirectional"))
      (node (ref "THERM20") (pin "1") (pinfunction "1_1") (pintype "bidirectional"))
    )
    (net (code "41") (name "/VCC_THERM1") (class "Default")
      (node (ref "THERM1") (pin "2") (pinfunction "2_2") (pintype "bidirectional"))
      (node (ref "VCC_THERM1") (pin "1") (pinfunction "P$1_1") (pintype "bidirectional"))
    )
    (net (code "42") (name "/VCC_THERM2") (class "Default")
      (node (ref "THERM2") (pin "2") (pinfunction "2_2") (pintype "bidirectional"))
      (node (ref "VCC_THERM2") (pin "1") (pinfunction "P$1_1") (pintype "bidirectional"))
    )
    (net (code "43") (name "/VCC_THERM3") (class "Default")
      (node (ref "THERM3") (pin "2") (pinfunction "2_2") (pintype "bidirectional"))
      (node (ref "VCC_THERM3") (pin "1") (pinfunction "P$1_1") (pintype "bidirectional"))
    )
    (net (code "44") (name "/VCC_THERM4") (class "Default")
      (node (ref "THERM4") (pin "2") (pinfunction "2_2") (pintype "bidirectional"))
      (node (ref "VCC_THERM4") (pin "1") (pinfunction "P$1_1") (pintype "bidirectional"))
    )
    (net (code "45") (name "/VCC_THERM5") (class "Default")
      (node (ref "THERM5") (pin "2") (pinfunction "2_2") (pintype "bidirectional"))
      (node (ref "VCC_THERM5") (pin "1") (pinfunction "P$1_1") (pintype "bidirectional"))
    )
    (net (code "46") (name "/VCC_THERM6") (class "Default")
      (node (ref "THERM6") (pin "2") (pinfunction "2_2") (pintype "bidirectional"))
      (node (ref "VCC_THERM6") (pin "1") (pinfunction "P$1_1") (pintype "bidirectional"))
    )
    (net (code "47") (name "/VCC_THERM7") (class "Default")
      (node (ref "THERM7") (pin "2") (pinfunction "2_2") (pintype "bidirectional"))
      (node (ref "VCC_THERM7") (pin "1") (pinfunction "P$1_1") (pintype "bidirectional"))
    )
    (net (code "48") (name "/VCC_THERM8") (class "Default")
      (node (ref "THERM8") (pin "2") (pinfunction "2_2") (pintype "bidirectional"))
      (node (ref "VCC_THERM8") (pin "1") (pinfunction "P$1_1") (pintype "bidirectional"))
    )
    (net (code "49") (name "/VCC_THERM9") (class "Default")
      (node (ref "THERM9") (pin "2") (pinfunction "2_2") (pintype "bidirectional"))
      (node (ref "VCC_THERM9") (pin "1") (pinfunction "P$1_1") (pintype "bidirectional"))
    )
    (net (code "50") (name "/VCC_THERM10") (class "Default")
      (node (ref "THERM10") (pin "2") (pinfunction "2_2") (pintype "bidirectional"))
      (node (ref "VCC_THERM10") (pin "1") (pinfunction "P$1_1") (pintype "bidirectional"))
    )
    (net (code "51") (name "/VCC_THERM11") (class "Default")
      (node (ref "THERM11") (pin "2") (pinfunction "2_2") (pintype "bidirectional"))
      (node (ref "VCC_THERM11") (pin "1") (pinfunction "P$1_1") (pintype "bidirectional"))
    )
    (net (code "52") (name "/VCC_THERM12") (class "Default")
      (node (ref "THERM12") (pin "2") (pinfunction "2_2") (pintype "bidirectional"))
      (node (ref "VCC_THERM12") (pin "1") (pinfunction "P$1_1") (pintype "bidirectional"))
    )
    (net (code "53") (name "/VCC_THERM13") (class "Default")
      (node (ref "THERM13") (pin "2") (pinfunction "2_2") (pintype "bidirectional"))
      (node (ref "VCC_THERM13") (pin "1") (pinfunction "P$1_1") (pintype "bidirectional"))
    )
    (net (code "54") (name "/VCC_THERM14") (class "Default")
      (node (ref "THERM14") (pin "2") (pinfunction "2_2") (pintype "bidirectional"))
      (node (ref "VCC_THERM14") (pin "1") (pinfunction "P$1_1") (pintype "bidirectional"))
    )
    (net (code "55") (name "/VCC_THERM15") (class "Default")
      (node (ref "THERM15") (pin "2") (pinfunction "2_2") (pintype "bidirectional"))
      (node (ref "VCC_THERM15") (pin "1") (pinfunction "P$1_1") (pintype "bidirectional"))
    )
    (net (code "56") (name "/VCC_THERM16") (class "Default")
      (node (ref "THERM16") (pin "2") (pinfunction "2_2") (pintype "bidirectional"))
      (node (ref "VCC_THERM16") (pin "1") (pinfunction "P$1_1") (pintype "bidirectional"))
    )
    (net (code "57") (name "/VCC_THERM17") (class "Default")
      (node (ref "THERM17") (pin "2") (pinfunction "2_2") (pintype "bidirectional"))
      (node (ref "VCC_THERM17") (pin "1") (pinfunction "P$1_1") (pintype "bidirectional"))
    )
    (net (code "58") (name "/VCC_THERM18") (class "Default")
      (node (ref "THERM18") (pin "2") (pinfunction "2_2") (pintype "bidirectional"))
      (node (ref "VCC_THERM18") (pin "1") (pinfunction "P$1_1") (pintype "bidirectional"))
    )
    (net (code "59") (name "/VCC_THERM19") (class "Default")
      (node (ref "THERM19") (pin "2") (pinfunction "2_2") (pintype "bidirectional"))
      (node (ref "VCC_THERM19") (pin "1") (pinfunction "P$1_1") (pintype "bidirectional"))
    )
    (net (code "60") (name "/VCC_THERM20") (class "Default")
      (node (ref "THERM20") (pin "2") (pinfunction "2_2") (pintype "bidirectional"))
      (node (ref "VCC_THERM20") (pin "1") (pinfunction "P$1_1") (pintype "bidirectional"))
    )
    (net (code "61") (name "/VRAW_HEAT1") (class "Default")
      (node (ref "VRAW_HEAT1") (pin "1") (pinfunction "P$1_1") (pintype "bidirectional"))
      (node (ref "VRAW_NICHROME1") (pin "P$1") (pinfunction "P$1_P$1") (pintype "bidirectional"))
    )
    (net (code "62") (name "/VRAW_HEAT2") (class "Default")
      (node (ref "VRAW_HEAT2") (pin "1") (pinfunction "P$1_1") (pintype "bidirectional"))
      (node (ref "VRAW_NICHROME2") (pin "P$1") (pinfunction "P$1_P$1") (pintype "bidirectional"))
    )
    (net (code "63") (name "/VRAW_HEAT3") (class "Default")
      (node (ref "VRAW_HEAT3") (pin "1") (pinfunction "P$1_1") (pintype "bidirectional"))
      (node (ref "VRAW_NICHROME3") (pin "P$1") (pinfunction "P$1_P$1") (pintype "bidirectional"))
    )
    (net (code "64") (name "/VRAW_HEAT4") (class "Default")
      (node (ref "VRAW_HEAT4") (pin "1") (pinfunction "P$1_1") (pintype "bidirectional"))
      (node (ref "VRAW_NICHROME4") (pin "P$1") (pinfunction "P$1_P$1") (pintype "bidirectional"))
    )
    (net (code "65") (name "/VRAW_HEAT5") (class "Default")
      (node (ref "VRAW_HEAT5") (pin "1") (pinfunction "P$1_1") (pintype "bidirectional"))
      (node (ref "VRAW_NICHROME5") (pin "P$1") (pinfunction "P$1_P$1") (pintype "bidirectional"))
    )
    (net (code "66") (name "/VRAW_HEAT6") (class "Default")
      (node (ref "VRAW_HEAT6") (pin "1") (pinfunction "P$1_1") (pintype "bidirectional"))
      (node (ref "VRAW_NICHROME6") (pin "P$1") (pinfunction "P$1_P$1") (pintype "bidirectional"))
    )
    (net (code "67") (name "/VRAW_HEAT7") (class "Default")
      (node (ref "VRAW_HEAT7") (pin "1") (pinfunction "P$1_1") (pintype "bidirectional"))
      (node (ref "VRAW_NICHROME7") (pin "P$1") (pinfunction "P$1_P$1") (pintype "bidirectional"))
    )
    (net (code "68") (name "/VRAW_HEAT8") (class "Default")
      (node (ref "VRAW_HEAT8") (pin "1") (pinfunction "P$1_1") (pintype "bidirectional"))
      (node (ref "VRAW_NICHROME8") (pin "P$1") (pinfunction "P$1_P$1") (pintype "bidirectional"))
    )
    (net (code "69") (name "/VRAW_HEAT9") (class "Default")
      (node (ref "VRAW_HEAT9") (pin "1") (pinfunction "P$1_1") (pintype "bidirectional"))
      (node (ref "VRAW_NICHROME9") (pin "P$1") (pinfunction "P$1_P$1") (pintype "bidirectional"))
    )
    (net (code "70") (name "/VRAW_HEAT10") (class "Default")
      (node (ref "VRAW_HEAT10") (pin "1") (pinfunction "P$1_1") (pintype "bidirectional"))
      (node (ref "VRAW_NICHROME10") (pin "P$1") (pinfunction "P$1_P$1") (pintype "bidirectional"))
    )
    (net (code "71") (name "/VRAW_HEAT11") (class "Default")
      (node (ref "VRAW_HEAT11") (pin "1") (pinfunction "P$1_1") (pintype "bidirectional"))
      (node (ref "VRAW_NICHROME11") (pin "P$1") (pinfunction "P$1_P$1") (pintype "bidirectional"))
    )
    (net (code "72") (name "/VRAW_HEAT12") (class "Default")
      (node (ref "VRAW_HEAT12") (pin "1") (pinfunction "P$1_1") (pintype "bidirectional"))
      (node (ref "VRAW_NICHROME12") (pin "P$1") (pinfunction "P$1_P$1") (pintype "bidirectional"))
    )
    (net (code "73") (name "/VRAW_HEAT13") (class "Default")
      (node (ref "VRAW_HEAT13") (pin "1") (pinfunction "P$1_1") (pintype "bidirectional"))
      (node (ref "VRAW_NICHROME13") (pin "P$1") (pinfunction "P$1_P$1") (pintype "bidirectional"))
    )
    (net (code "74") (name "/VRAW_HEAT14") (class "Default")
      (node (ref "VRAW_HEAT14") (pin "1") (pinfunction "P$1_1") (pintype "bidirectional"))
      (node (ref "VRAW_NICHROME14") (pin "P$1") (pinfunction "P$1_P$1") (pintype "bidirectional"))
    )
    (net (code "75") (name "/VRAW_HEAT15") (class "Default")
      (node (ref "VRAW_HEAT15") (pin "1") (pinfunction "P$1_1") (pintype "bidirectional"))
      (node (ref "VRAW_NICHROME15") (pin "P$1") (pinfunction "P$1_P$1") (pintype "bidirectional"))
    )
    (net (code "76") (name "/VRAW_HEAT16") (class "Default")
      (node (ref "VRAW_HEAT16") (pin "1") (pinfunction "P$1_1") (pintype "bidirectional"))
      (node (ref "VRAW_NICHROME16") (pin "P$1") (pinfunction "P$1_P$1") (pintype "bidirectional"))
    )
    (net (code "77") (name "/VRAW_HEAT17") (class "Default")
      (node (ref "VRAW_HEAT17") (pin "1") (pinfunction "P$1_1") (pintype "bidirectional"))
      (node (ref "VRAW_NICHROME17") (pin "P$1") (pinfunction "P$1_P$1") (pintype "bidirectional"))
    )
    (net (code "78") (name "/VRAW_HEAT18") (class "Default")
      (node (ref "VRAW_HEAT18") (pin "1") (pinfunction "P$1_1") (pintype "bidirectional"))
      (node (ref "VRAW_NICHROME18") (pin "P$1") (pinfunction "P$1_P$1") (pintype "bidirectional"))
    )
    (net (code "79") (name "/VRAW_HEAT19") (class "Default")
      (node (ref "VRAW_HEAT19") (pin "1") (pinfunction "P$1_1") (pintype "bidirectional"))
      (node (ref "VRAW_NICHROME19") (pin "P$1") (pinfunction "P$1_P$1") (pintype "bidirectional"))
    )
    (net (code "80") (name "/VRAW_HEAT20") (class "Default")
      (node (ref "VRAW_HEAT20") (pin "1") (pinfunction "P$1_1") (pintype "bidirectional"))
      (node (ref "VRAW_NICHROME20") (pin "P$1") (pinfunction "P$1_P$1") (pintype "bidirectional"))
    )
  )
)
